# rs485_usb.net
KiCad netlist of a schematic drawn in EAGLE
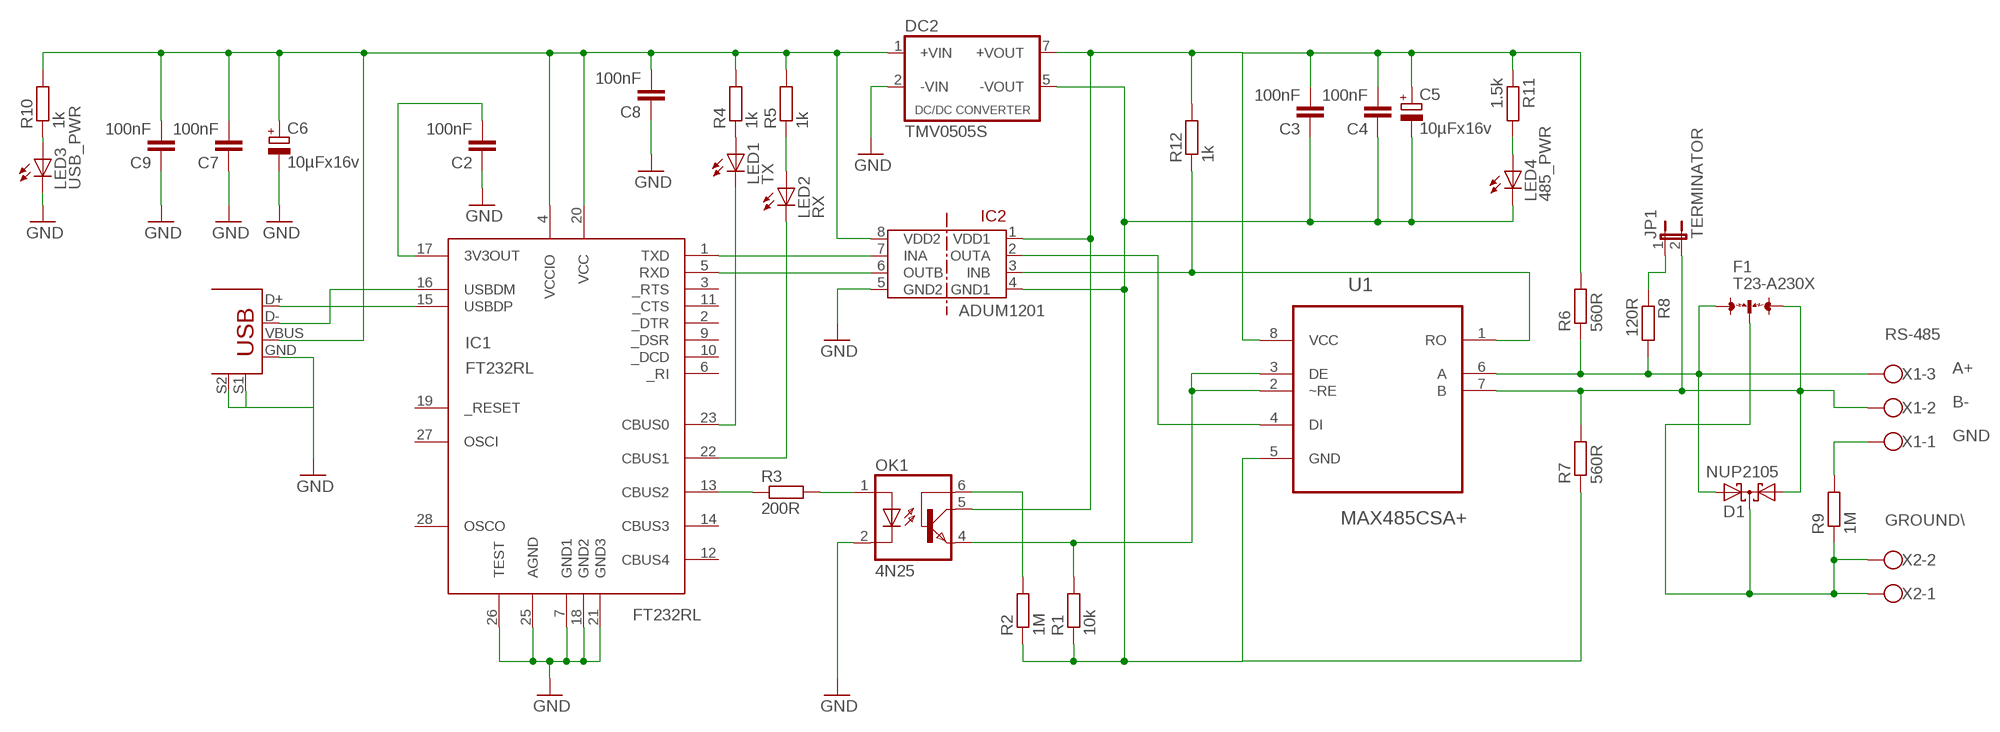
[diagram p0: schematic, sheet 1]

(export (version "E")
  (design (tool "Eeschema 10.0.6"))
  (components
    (comp (ref "C2")
      (value "100nF")
      (footprint "eagle-import:C0603")
      (libsource (lib "eagle-import") (part "C-EUC0603"))
    )
    (comp (ref "C3")
      (value "100nF")
      (footprint "eagle-import:C0805")
      (libsource (lib "eagle-import") (part "C-EUC0805"))
    )
    (comp (ref "C4")
      (value "100nF")
      (footprint "eagle-import:C0805")
      (libsource (lib "eagle-import") (part "C-EUC0805"))
    )
    (comp (ref "C5")
      (value "10µFx16v")
      (footprint "eagle-import:E2,5-6E")
      (libsource (lib "eagle-import") (part "CPOL-EUE2,5-6E"))
    )
    (comp (ref "C6")
      (value "10µFx16v")
      (footprint "eagle-import:E2,5-6E")
      (libsource (lib "eagle-import") (part "CPOL-EUE2,5-6E"))
    )
    (comp (ref "C7")
      (value "100nF")
      (footprint "eagle-import:C0805")
      (libsource (lib "eagle-import") (part "C-EUC0805"))
    )
    (comp (ref "C8")
      (value "100nF")
      (footprint "eagle-import:C0805")
      (libsource (lib "eagle-import") (part "C-EUC0805"))
    )
    (comp (ref "C9")
      (value "100nF")
      (footprint "eagle-import:C0805")
      (libsource (lib "eagle-import") (part "C-EUC0805"))
    )
    (comp (ref "D1")
      (value "NUP2105")
      (footprint "eagle-import:SOT23")
      (libsource (lib "eagle-import") (part "BAS70-05"))
    )
    (comp (ref "DC2")
      (value "TMV0505S")
      (footprint "eagle-import:NMKXXXXSAC")
      (libsource (lib "eagle-import") (part "NMKXXXXSAC"))
    )
    (comp (ref "F1")
      (value "T23-A230X")
      (footprint "eagle-import:T23-A230X")
      (libsource (lib "eagle-import") (part "T23-A230X"))
    )
    (comp (ref "IC1")
      (value "FT232RL")
      (footprint "eagle-import:SSOP28DB")
      (libsource (lib "eagle-import") (part "FT232RL"))
    )
    (comp (ref "IC2")
      (value "ADUM1201")
      (footprint "eagle-import:SO8")
      (libsource (lib "eagle-import") (part "ADUM1201"))
    )
    (comp (ref "JP1")
      (value "TERMINATOR")
      (footprint "eagle-import:JP1")
      (libsource (lib "eagle-import") (part "JP1E"))
    )
    (comp (ref "LED1")
      (value "TX")
      (footprint "eagle-import:LED3MM")
      (libsource (lib "eagle-import") (part "LED3MM"))
    )
    (comp (ref "LED2")
      (value "RX")
      (footprint "eagle-import:LED3MM")
      (libsource (lib "eagle-import") (part "LED3MM"))
    )
    (comp (ref "LED3")
      (value "USB_PWR")
      (footprint "eagle-import:LED3MM")
      (libsource (lib "eagle-import") (part "LED3MM"))
    )
    (comp (ref "LED4")
      (value "485_PWR")
      (footprint "eagle-import:LED3MM")
      (libsource (lib "eagle-import") (part "LED3MM"))
    )
    (comp (ref "OK1")
      (value "4N25")
      (footprint "eagle-import:DIL06")
      (fields (field (name "MF") "FAIRCHILD SEMICONDUCTOR") (field (name "MPN") "4N35"))
      (libsource (lib "eagle-import") (part "4N35"))
    )
    (comp (ref "R1")
      (value "10k")
      (footprint "eagle-import:0204_5")
      (libsource (lib "eagle-import") (part "R-EU_0204/5"))
    )
    (comp (ref "R2")
      (value "1M")
      (footprint "eagle-import:R0603")
      (libsource (lib "eagle-import") (part "R-EU_R0603"))
    )
    (comp (ref "R3")
      (value "200R")
      (footprint "eagle-import:R0603")
      (libsource (lib "eagle-import") (part "R-EU_R0603"))
    )
    (comp (ref "R4")
      (value "1k")
      (footprint "eagle-import:R0805")
      (libsource (lib "eagle-import") (part "R-EU_R0805"))
    )
    (comp (ref "R5")
      (value "1k")
      (footprint "eagle-import:R0805")
      (libsource (lib "eagle-import") (part "R-EU_R0805"))
    )
    (comp (ref "R6")
      (value "560R")
      (footprint "eagle-import:R0603")
      (libsource (lib "eagle-import") (part "R-EU_R0603"))
    )
    (comp (ref "R7")
      (value "560R")
      (footprint "eagle-import:R0603")
      (libsource (lib "eagle-import") (part "R-EU_R0603"))
    )
    (comp (ref "R8")
      (value "120R")
      (footprint "eagle-import:R0603")
      (libsource (lib "eagle-import") (part "R-EU_R0603"))
    )
    (comp (ref "R9")
      (value "1M")
      (footprint "eagle-import:0207_2V")
      (libsource (lib "eagle-import") (part "resistor_R-EU_0207/2V"))
    )
    (comp (ref "R10")
      (value "1k")
      (footprint "eagle-import:R0805")
      (libsource (lib "eagle-import") (part "R-EU_R0805"))
    )
    (comp (ref "R11")
      (value "1.5k")
      (footprint "eagle-import:R0805")
      (libsource (lib "eagle-import") (part "R-EU_R0805"))
    )
    (comp (ref "R12")
      (value "1k")
      (footprint "eagle-import:R0805")
      (libsource (lib "eagle-import") (part "R-EU_R0805"))
    )
    (comp (ref "U$1")
      (value "USB+SHIELD")
      (footprint "eagle-import:USB-B-PTH")
      (libsource (lib "eagle-import") (part "USB+SHIELD"))
    )
    (comp (ref "U1")
      (value "MAX485CSA+")
      (footprint "eagle-import:SOIC127P600X175-8N")
      (libsource (lib "eagle-import") (part "MAX485CSA+"))
    )
    (comp (ref "X1")
      (value "W237-103")
      (footprint "eagle-import:W237-103")
      (fields (field (name "MPN") "237-103"))
      (libsource (lib "eagle-import") (part "W237-103"))
    )
    (comp (ref "X2")
      (value "W237-102")
      (footprint "eagle-import:W237-102")
      (fields (field (name "MPN") "237-102"))
      (libsource (lib "eagle-import") (part "W237-102"))
    )
  )
  (nets
    (net (code "1") (name "GND") (class "Default")
      (node (ref "C2") (pin "1") (pinfunction "1_1") (pintype "passive"))
      (node (ref "C6") (pin "-") (pinfunction "-_-") (pintype "passive"))
      (node (ref "C7") (pin "1") (pinfunction "1_1") (pintype "passive"))
      (node (ref "C8") (pin "1") (pinfunction "1_1") (pintype "passive"))
      (node (ref "C9") (pin "1") (pinfunction "1_1") (pintype "passive"))
      (node (ref "DC2") (pin "2") (pinfunction "-VIN_2") (pintype "passive"))
      (node (ref "IC1") (pin "18") (pinfunction "GND2_18") (pintype "power_in"))
      (node (ref "IC1") (pin "21") (pinfunction "GND3_21") (pintype "power_in"))
      (node (ref "IC1") (pin "25") (pinfunction "AGND_25") (pintype "power_in"))
      (node (ref "IC1") (pin "26") (pinfunction "TEST_26") (pintype "input"))
      (node (ref "IC1") (pin "7") (pinfunction "GND1_7") (pintype "power_in"))
      (node (ref "IC2") (pin "5") (pinfunction "GND2_5") (pintype "power_in"))
      (node (ref "LED3") (pin "K") (pinfunction "C_K") (pintype "passive"))
      (node (ref "OK1") (pin "2") (pinfunction "C_2") (pintype "passive"))
      (node (ref "U$1") (pin "GND") (pinfunction "GND_GND") (pintype "bidirectional"))
      (node (ref "U$1") (pin "S1") (pinfunction "S1_S1") (pintype "bidirectional"))
      (node (ref "U$1") (pin "S2") (pinfunction "S2_S2") (pintype "bidirectional"))
    )
    (net (code "2") (name "Net-(D1-A1)") (class "Default")
      (node (ref "D1") (pin "1") (pinfunction "A1_1") (pintype "passive"))
      (node (ref "F1") (pin "3") (pinfunction "3_3") (pintype "passive"))
      (node (ref "JP1") (pin "2") (pinfunction "2_2") (pintype "passive"))
      (node (ref "R7") (pin "2") (pinfunction "2_2") (pintype "passive"))
      (node (ref "U1") (pin "7") (pinfunction "B_7") (pintype "bidirectional"))
      (node (ref "X1") (pin "2") (pinfunction "KL_2") (pintype "passive"))
    )
    (net (code "3") (name "Net-(D1-A2)") (class "Default")
      (node (ref "D1") (pin "2") (pinfunction "A2_2") (pintype "passive"))
      (node (ref "F1") (pin "1") (pinfunction "1_1") (pintype "passive"))
      (node (ref "R6") (pin "1") (pinfunction "1_1") (pintype "passive"))
      (node (ref "R8") (pin "2") (pinfunction "2_2") (pintype "passive"))
      (node (ref "U1") (pin "6") (pinfunction "A_6") (pintype "bidirectional"))
      (node (ref "X1") (pin "3") (pinfunction "KL_3") (pintype "passive"))
    )
    (net (code "4") (name "Net-(D1-C)") (class "Default")
      (node (ref "D1") (pin "3") (pinfunction "C_3") (pintype "passive"))
      (node (ref "F1") (pin "2") (pinfunction "2_2") (pintype "passive"))
      (node (ref "R9") (pin "1") (pinfunction "1_1") (pintype "passive"))
      (node (ref "X2") (pin "1") (pinfunction "KL_1") (pintype "passive"))
      (node (ref "X2") (pin "2") (pinfunction "KL_2") (pintype "passive"))
    )
    (net (code "5") (name "Net-(DC2-+VIN)") (class "Default")
      (node (ref "C6") (pin "+") (pinfunction "+_+") (pintype "passive"))
      (node (ref "C7") (pin "2") (pinfunction "2_2") (pintype "passive"))
      (node (ref "C8") (pin "2") (pinfunction "2_2") (pintype "passive"))
      (node (ref "C9") (pin "2") (pinfunction "2_2") (pintype "passive"))
      (node (ref "DC2") (pin "1") (pinfunction "+VIN_1") (pintype "passive"))
      (node (ref "IC1") (pin "20") (pinfunction "VCC_20") (pintype "power_in"))
      (node (ref "IC1") (pin "4") (pinfunction "VCCIO_4") (pintype "power_in"))
      (node (ref "IC2") (pin "8") (pinfunction "VDD2_8") (pintype "power_in"))
      (node (ref "R10") (pin "2") (pinfunction "2_2") (pintype "passive"))
      (node (ref "R4") (pin "2") (pinfunction "2_2") (pintype "passive"))
      (node (ref "R5") (pin "2") (pinfunction "2_2") (pintype "passive"))
      (node (ref "U$1") (pin "VBUS") (pinfunction "VBUS_VBUS") (pintype "bidirectional"))
    )
    (net (code "6") (name "Net-(DC2-+VOUT)") (class "Default")
      (node (ref "C3") (pin "2") (pinfunction "2_2") (pintype "passive"))
      (node (ref "C4") (pin "2") (pinfunction "2_2") (pintype "passive"))
      (node (ref "C5") (pin "+") (pinfunction "+_+") (pintype "passive"))
      (node (ref "DC2") (pin "7") (pinfunction "+VOUT_7") (pintype "passive"))
      (node (ref "IC2") (pin "1") (pinfunction "VDD1_1") (pintype "power_in"))
      (node (ref "OK1") (pin "5") (pinfunction "COL_5") (pintype "passive"))
      (node (ref "R11") (pin "1") (pinfunction "1_1") (pintype "passive"))
      (node (ref "R12") (pin "2") (pinfunction "2_2") (pintype "passive"))
      (node (ref "R6") (pin "2") (pinfunction "2_2") (pintype "passive"))
      (node (ref "U1") (pin "8") (pinfunction "VCC_8") (pintype "power_in"))
    )
    (net (code "7") (name "Net-(DC2--VOUT)") (class "Default")
      (node (ref "C3") (pin "1") (pinfunction "1_1") (pintype "passive"))
      (node (ref "C4") (pin "1") (pinfunction "1_1") (pintype "passive"))
      (node (ref "C5") (pin "-") (pinfunction "-_-") (pintype "passive"))
      (node (ref "DC2") (pin "5") (pinfunction "-VOUT_5") (pintype "passive"))
      (node (ref "IC2") (pin "4") (pinfunction "GND1_4") (pintype "power_in"))
      (node (ref "LED4") (pin "K") (pinfunction "C_K") (pintype "passive"))
      (node (ref "R1") (pin "1") (pinfunction "1_1") (pintype "passive"))
      (node (ref "R2") (pin "1") (pinfunction "1_1") (pintype "passive"))
      (node (ref "R7") (pin "1") (pinfunction "1_1") (pintype "passive"))
      (node (ref "U1") (pin "5") (pinfunction "GND_5") (pintype "passive"))
    )
    (net (code "8") (name "Net-(IC1-3V3OUT)") (class "Default")
      (node (ref "C2") (pin "2") (pinfunction "2_2") (pintype "passive"))
      (node (ref "IC1") (pin "17") (pinfunction "3V3OUT_17") (pintype "output"))
    )
    (net (code "9") (name "Net-(IC1-CBUS0)") (class "Default")
      (node (ref "IC1") (pin "23") (pinfunction "CBUS0_23") (pintype "bidirectional"))
      (node (ref "LED1") (pin "K") (pinfunction "C_K") (pintype "passive"))
    )
    (net (code "10") (name "Net-(IC1-CBUS1)") (class "Default")
      (node (ref "IC1") (pin "22") (pinfunction "CBUS1_22") (pintype "bidirectional"))
      (node (ref "LED2") (pin "K") (pinfunction "C_K") (pintype "passive"))
    )
    (net (code "11") (name "Net-(IC1-CBUS2)") (class "Default")
      (node (ref "IC1") (pin "13") (pinfunction "CBUS2_13") (pintype "bidirectional"))
      (node (ref "R3") (pin "1") (pinfunction "1_1") (pintype "passive"))
    )
    (net (code "12") (name "Net-(IC1-RXD)") (class "Default")
      (node (ref "IC1") (pin "5") (pinfunction "RXD_5") (pintype "input"))
      (node (ref "IC2") (pin "6") (pinfunction "OUTB_6") (pintype "output"))
    )
    (net (code "13") (name "Net-(IC1-TXD)") (class "Default")
      (node (ref "IC1") (pin "1") (pinfunction "TXD_1") (pintype "output"))
      (node (ref "IC2") (pin "7") (pinfunction "INA_7") (pintype "input"))
    )
    (net (code "14") (name "Net-(IC1-USBDM)") (class "Default")
      (node (ref "IC1") (pin "16") (pinfunction "USBDM_16") (pintype "bidirectional"))
      (node (ref "U$1") (pin "D-") (pinfunction "D-_D-") (pintype "bidirectional"))
    )
    (net (code "15") (name "Net-(IC1-USBDP)") (class "Default")
      (node (ref "IC1") (pin "15") (pinfunction "USBDP_15") (pintype "bidirectional"))
      (node (ref "U$1") (pin "D+") (pinfunction "D+_D+") (pintype "bidirectional"))
    )
    (net (code "16") (name "Net-(IC2-INB)") (class "Default")
      (node (ref "IC2") (pin "3") (pinfunction "INB_3") (pintype "input"))
      (node (ref "R12") (pin "1") (pinfunction "1_1") (pintype "passive"))
      (node (ref "U1") (pin "1") (pinfunction "RO_1") (pintype "output"))
    )
    (net (code "17") (name "Net-(IC2-OUTA)") (class "Default")
      (node (ref "IC2") (pin "2") (pinfunction "OUTA_2") (pintype "output"))
      (node (ref "U1") (pin "4") (pinfunction "DI_4") (pintype "input"))
    )
    (net (code "18") (name "Net-(JP1-Pad1)") (class "Default")
      (node (ref "JP1") (pin "1") (pinfunction "1_1") (pintype "passive"))
      (node (ref "R8") (pin "1") (pinfunction "1_1") (pintype "passive"))
    )
    (net (code "19") (name "Net-(LED1-PadA)") (class "Default")
      (node (ref "LED1") (pin "A") (pinfunction "A_A") (pintype "passive"))
      (node (ref "R4") (pin "1") (pinfunction "1_1") (pintype "passive"))
    )
    (net (code "20") (name "Net-(LED2-PadA)") (class "Default")
      (node (ref "LED2") (pin "A") (pinfunction "A_A") (pintype "passive"))
      (node (ref "R5") (pin "1") (pinfunction "1_1") (pintype "passive"))
    )
    (net (code "21") (name "Net-(LED3-PadA)") (class "Default")
      (node (ref "LED3") (pin "A") (pinfunction "A_A") (pintype "passive"))
      (node (ref "R10") (pin "1") (pinfunction "1_1") (pintype "passive"))
    )
    (net (code "22") (name "Net-(LED4-PadA)") (class "Default")
      (node (ref "LED4") (pin "A") (pinfunction "A_A") (pintype "passive"))
      (node (ref "R11") (pin "2") (pinfunction "2_2") (pintype "passive"))
    )
    (net (code "23") (name "Net-(OK1-A)") (class "Default")
      (node (ref "OK1") (pin "1") (pinfunction "A_1") (pintype "passive"))
      (node (ref "R3") (pin "2") (pinfunction "2_2") (pintype "passive"))
    )
    (net (code "24") (name "Net-(OK1-BAS)") (class "Default")
      (node (ref "OK1") (pin "6") (pinfunction "BAS_6") (pintype "passive"))
      (node (ref "R2") (pin "2") (pinfunction "2_2") (pintype "passive"))
    )
    (net (code "25") (name "Net-(OK1-EMI)") (class "Default")
      (node (ref "OK1") (pin "4") (pinfunction "EMI_4") (pintype "passive"))
      (node (ref "R1") (pin "2") (pinfunction "2_2") (pintype "passive"))
      (node (ref "U1") (pin "2") (pinfunction "~{RE}_2") (pintype "input"))
      (node (ref "U1") (pin "3") (pinfunction "DE_3") (pintype "input"))
    )
    (net (code "26") (name "Net-(X1A-KL)") (class "Default")
      (node (ref "R9") (pin "2") (pinfunction "2_2") (pintype "passive"))
      (node (ref "X1") (pin "1") (pinfunction "KL_1") (pintype "passive"))
    )
    (net (code "27") (name "unconnected-(IC1-CBUS3-Pad14)") (class "Default")
      (node (ref "IC1") (pin "14") (pinfunction "CBUS3_14") (pintype "bidirectional"))
    )
    (net (code "28") (name "unconnected-(IC1-CBUS4-Pad12)") (class "Default")
      (node (ref "IC1") (pin "12") (pinfunction "CBUS4_12") (pintype "bidirectional"))
    )
    (net (code "29") (name "unconnected-(IC1-OSCI-Pad27)") (class "Default")
      (node (ref "IC1") (pin "27") (pinfunction "OSCI_27") (pintype "input"))
    )
    (net (code "30") (name "unconnected-(IC1-OSCO-Pad28)") (class "Default")
      (node (ref "IC1") (pin "28") (pinfunction "OSCO_28") (pintype "output"))
    )
    (net (code "31") (name "unconnected-(IC1-_CTS-Pad11)") (class "Default")
      (node (ref "IC1") (pin "11") (pinfunction "_CTS_11") (pintype "input"))
    )
    (net (code "32") (name "unconnected-(IC1-_DCD-Pad10)") (class "Default")
      (node (ref "IC1") (pin "10") (pinfunction "_DCD_10") (pintype "input"))
    )
    (net (code "33") (name "unconnected-(IC1-_DSR-Pad9)") (class "Default")
      (node (ref "IC1") (pin "9") (pinfunction "_DSR_9") (pintype "input"))
    )
    (net (code "34") (name "unconnected-(IC1-_DTR-Pad2)") (class "Default")
      (node (ref "IC1") (pin "2") (pinfunction "_DTR_2") (pintype "output"))
    )
    (net (code "35") (name "unconnected-(IC1-_RESET-Pad19)") (class "Default")
      (node (ref "IC1") (pin "19") (pinfunction "_RESET_19") (pintype "input"))
    )
    (net (code "36") (name "unconnected-(IC1-_RI-Pad6)") (class "Default")
      (node (ref "IC1") (pin "6") (pinfunction "_RI_6") (pintype "input"))
    )
    (net (code "37") (name "unconnected-(IC1-_RTS-Pad3)") (class "Default")
      (node (ref "IC1") (pin "3") (pinfunction "_RTS_3") (pintype "output"))
    )
  )
)
